# Sheet1.net
KiCad netlist of a schematic drawn in Altium Designer
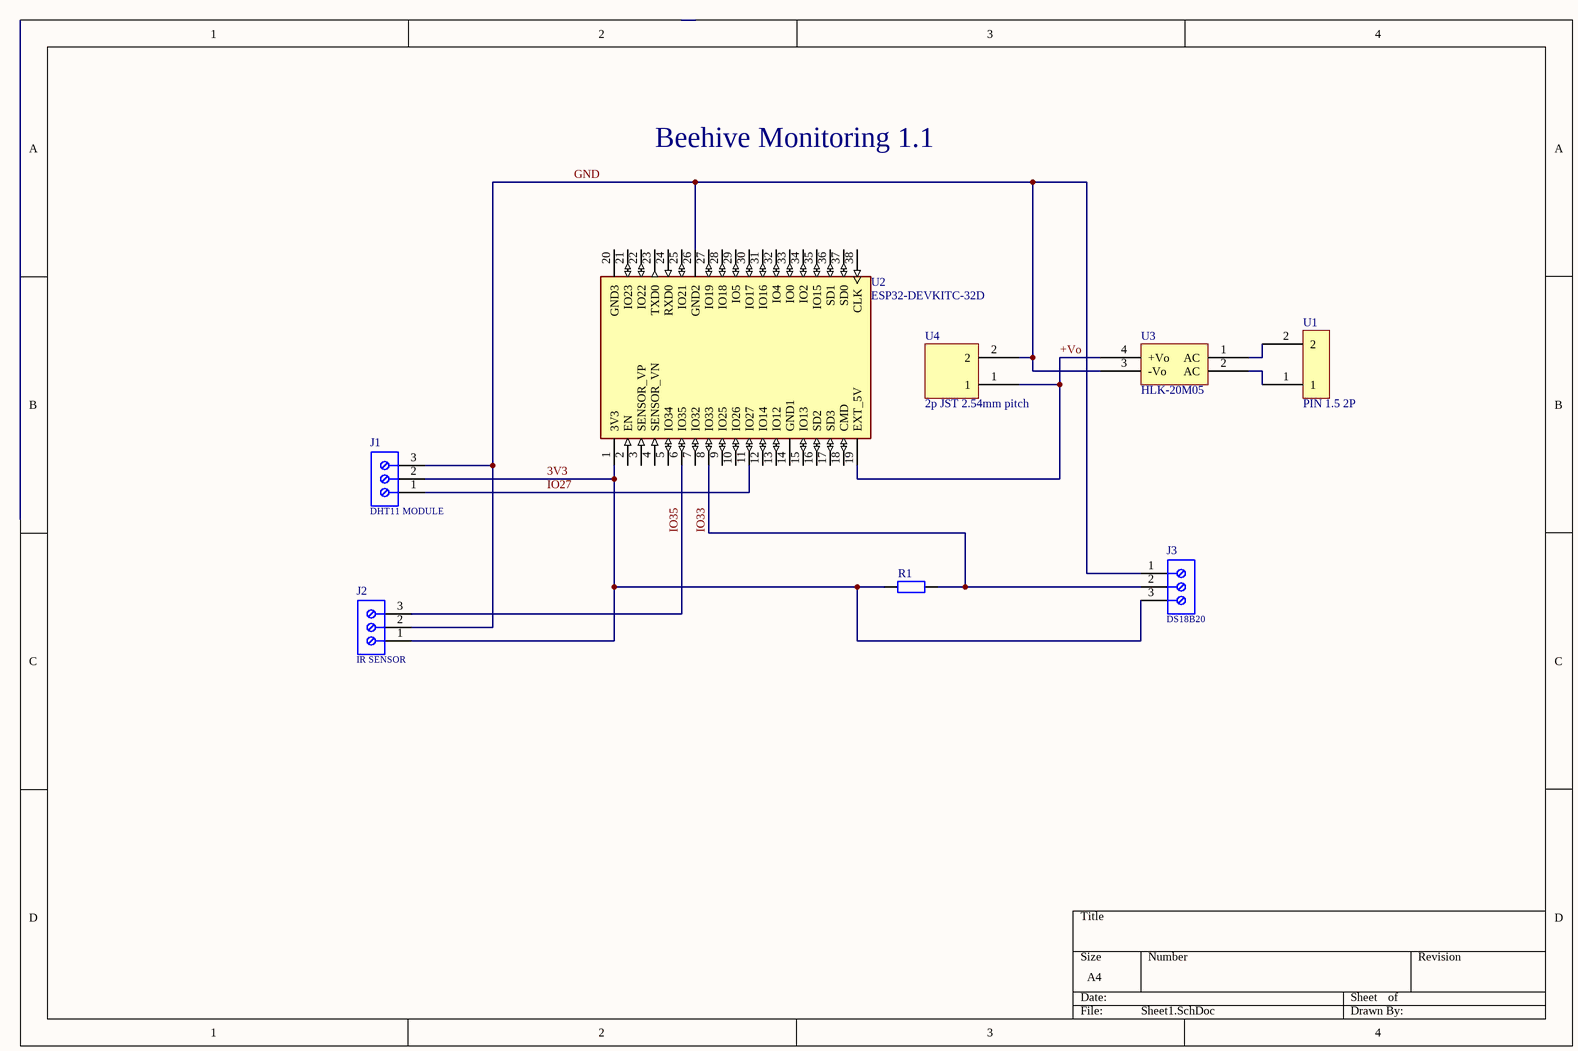
[diagram p0: Sheet1.SchDoc]

(export (version "E")
  (design (tool "Eeschema 10.0.6"))
  (components
    (comp (ref "J1")
      (value "DHT11 MODULE")
      (footprint "691214110003")
      (description "Serie 2141 - 3.50 mm Horizontal Entry Modular with Rising Cage Clamp WR-TBL, 3 pin")
      (fields
        (field (name "MANUFACTURER") "Wurth Elektronik")
        (field (name "PART NUMBER") "691214110003")
        (field (name "PUBLISHER") "WurthElektronik")
      )
      (libsource (lib "Altium Content Vault") (part "WE-CN-1P-F-TB3"))
    )
    (comp (ref "J2")
      (value "IR SENSOR")
      (footprint "691214110003")
      (description "Serie 2141 - 3.50 mm Horizontal Entry Modular with Rising Cage Clamp WR-TBL, 3 pin")
      (fields
        (field (name "MANUFACTURER") "Wurth Elektronik")
        (field (name "PART NUMBER") "691214110003")
        (field (name "PUBLISHER") "WurthElektronik")
      )
      (libsource (lib "Altium Content Vault") (part "WE-CN-1P-F-TB3"))
    )
    (comp (ref "J3")
      (value "DS18B20")
      (footprint "691214110003")
      (description "Serie 2141 - 3.50 mm Horizontal Entry Modular with Rising Cage Clamp WR-TBL, 3 pin")
      (fields
        (field (name "MANUFACTURER") "Wurth Elektronik")
        (field (name "PART NUMBER") "691214110003")
        (field (name "PUBLISHER") "WurthElektronik")
      )
      (libsource (lib "Altium Content Vault") (part "WE-CN-1P-F-TB3"))
    )
    (comp (ref "R1")
      (value "Res2")
      (footprint "AXIAL-0.4")
      (description "Resistor")
      (fields (field (name "PUBLISHER") "Altium Limited"))
      (libsource (lib "Miscellaneous Devices") (part "Res2"))
    )
    (comp (ref "U1")
      (value "PIN 1.5 2P")
      (footprint "PIN 1.5MM 2PIN")
      (description "BORNERA 1.5MM 2.8MM 2P")
      (libsource (lib "Schlib1") (part "PIN 1.5 2P"))
    )
    (comp (ref "U2")
      (value "ESP32-DEVKITC-32D")
      (footprint "MODULE_ESP32-DEVKITC-32D")
      (description "EVAL BOARD FOR ESP-WROOM-32")
      (fields (field (name "MF") "Espressif Systems"))
      (libsource (lib "ESP32-DEVKITC-32D") (part "ESP32-DEVKITC-32D"))
    )
    (comp (ref "U3")
      (value "HLK-20M05")
      (footprint "HLK-20M05")
      (libsource (lib "Schlib1") (part "HLK-20M05"))
    )
    (comp (ref "U4")
      (value "2p JST 2.54mm pitch")
      (footprint "PCBComponent_1")
      (libsource (lib "Schlib1") (part "Component_1"))
    )
  )
  (nets
    (net (code "1") (name "/+Vo") (class "Default")
      (node (ref "U2") (pin "19") (pinfunction "EXT_5V_19") (pintype "power_in"))
      (node (ref "U3") (pin "4") (pinfunction "+Vo_4") (pintype "passive"))
      (node (ref "U4") (pin "1") (pinfunction "1_1") (pintype "passive"))
    )
    (net (code "2") (name "/3V3") (class "Default")
      (node (ref "J1") (pin "2") (pinfunction "2_2") (pintype "passive"))
      (node (ref "J2") (pin "1") (pinfunction "1_1") (pintype "passive"))
      (node (ref "J3") (pin "3") (pinfunction "3_3") (pintype "passive"))
      (node (ref "R1") (pin "1") (pinfunction "1_1") (pintype "passive"))
      (node (ref "U2") (pin "1") (pinfunction "3V3_1") (pintype "power_in"))
    )
    (net (code "3") (name "/GND") (class "Default")
      (node (ref "J1") (pin "3") (pinfunction "3_3") (pintype "passive"))
      (node (ref "J2") (pin "2") (pinfunction "2_2") (pintype "passive"))
      (node (ref "J3") (pin "1") (pinfunction "1_1") (pintype "passive"))
      (node (ref "U2") (pin "26") (pinfunction "GND2_26") (pintype "power_in"))
      (node (ref "U3") (pin "3") (pinfunction "-Vo_3") (pintype "passive"))
      (node (ref "U4") (pin "2") (pinfunction "2_2") (pintype "passive"))
    )
    (net (code "4") (name "/IO27") (class "Default")
      (node (ref "J1") (pin "1") (pinfunction "1_1") (pintype "passive"))
      (node (ref "U2") (pin "11") (pinfunction "IO27_11") (pintype "bidirectional"))
    )
    (net (code "5") (name "/IO33") (class "Default")
      (node (ref "J3") (pin "2") (pinfunction "2_2") (pintype "passive"))
      (node (ref "R1") (pin "2") (pinfunction "2_2") (pintype "passive"))
      (node (ref "U2") (pin "8") (pinfunction "IO33_8") (pintype "bidirectional"))
    )
    (net (code "6") (name "/IO35") (class "Default")
      (node (ref "J2") (pin "3") (pinfunction "3_3") (pintype "passive"))
      (node (ref "U2") (pin "6") (pinfunction "IO35_6") (pintype "bidirectional"))
    )
    (net (code "7") (name "Net-(U1-Pad1)") (class "Default")
      (node (ref "U1") (pin "1") (pinfunction "1_1") (pintype "passive"))
      (node (ref "U3") (pin "2") (pinfunction "AC_2") (pintype "passive"))
    )
    (net (code "8") (name "Net-(U1-Pad2)") (class "Default")
      (node (ref "U1") (pin "2") (pinfunction "2_2") (pintype "passive"))
      (node (ref "U3") (pin "1") (pinfunction "AC_1") (pintype "passive"))
    )
    (net (code "9") (name "unconnected-(U2-CLK-Pad38)") (class "Default")
      (node (ref "U2") (pin "38") (pinfunction "CLK_38") (pintype "input"))
    )
    (net (code "10") (name "unconnected-(U2-CMD-Pad18)") (class "Default")
      (node (ref "U2") (pin "18") (pinfunction "CMD_18") (pintype "bidirectional"))
    )
    (net (code "11") (name "unconnected-(U2-EN-Pad2)") (class "Default")
      (node (ref "U2") (pin "2") (pinfunction "EN_2") (pintype "input"))
    )
    (net (code "12") (name "unconnected-(U2-GND1-Pad14)") (class "Default")
      (node (ref "U2") (pin "14") (pinfunction "GND1_14") (pintype "power_in"))
    )
    (net (code "13") (name "unconnected-(U2-GND3-Pad20)") (class "Default")
      (node (ref "U2") (pin "20") (pinfunction "GND3_20") (pintype "power_in"))
    )
    (net (code "14") (name "unconnected-(U2-IO0-Pad33)") (class "Default")
      (node (ref "U2") (pin "33") (pinfunction "IO0_33") (pintype "bidirectional"))
    )
    (net (code "15") (name "unconnected-(U2-IO2-Pad34)") (class "Default")
      (node (ref "U2") (pin "34") (pinfunction "IO2_34") (pintype "bidirectional"))
    )
    (net (code "16") (name "unconnected-(U2-IO4-Pad32)") (class "Default")
      (node (ref "U2") (pin "32") (pinfunction "IO4_32") (pintype "bidirectional"))
    )
    (net (code "17") (name "unconnected-(U2-IO5-Pad29)") (class "Default")
      (node (ref "U2") (pin "29") (pinfunction "IO5_29") (pintype "bidirectional"))
    )
    (net (code "18") (name "unconnected-(U2-IO12-Pad13)") (class "Default")
      (node (ref "U2") (pin "13") (pinfunction "IO12_13") (pintype "bidirectional"))
    )
    (net (code "19") (name "unconnected-(U2-IO13-Pad15)") (class "Default")
      (node (ref "U2") (pin "15") (pinfunction "IO13_15") (pintype "bidirectional"))
    )
    (net (code "20") (name "unconnected-(U2-IO14-Pad12)") (class "Default")
      (node (ref "U2") (pin "12") (pinfunction "IO14_12") (pintype "bidirectional"))
    )
    (net (code "21") (name "unconnected-(U2-IO15-Pad35)") (class "Default")
      (node (ref "U2") (pin "35") (pinfunction "IO15_35") (pintype "bidirectional"))
    )
    (net (code "22") (name "unconnected-(U2-IO16-Pad31)") (class "Default")
      (node (ref "U2") (pin "31") (pinfunction "IO16_31") (pintype "bidirectional"))
    )
    (net (code "23") (name "unconnected-(U2-IO17-Pad30)") (class "Default")
      (node (ref "U2") (pin "30") (pinfunction "IO17_30") (pintype "bidirectional"))
    )
    (net (code "24") (name "unconnected-(U2-IO18-Pad28)") (class "Default")
      (node (ref "U2") (pin "28") (pinfunction "IO18_28") (pintype "bidirectional"))
    )
    (net (code "25") (name "unconnected-(U2-IO19-Pad27)") (class "Default")
      (node (ref "U2") (pin "27") (pinfunction "IO19_27") (pintype "bidirectional"))
    )
    (net (code "26") (name "unconnected-(U2-IO21-Pad25)") (class "Default")
      (node (ref "U2") (pin "25") (pinfunction "IO21_25") (pintype "bidirectional"))
    )
    (net (code "27") (name "unconnected-(U2-IO22-Pad22)") (class "Default")
      (node (ref "U2") (pin "22") (pinfunction "IO22_22") (pintype "bidirectional"))
    )
    (net (code "28") (name "unconnected-(U2-IO23-Pad21)") (class "Default")
      (node (ref "U2") (pin "21") (pinfunction "IO23_21") (pintype "bidirectional"))
    )
    (net (code "29") (name "unconnected-(U2-IO25-Pad9)") (class "Default")
      (node (ref "U2") (pin "9") (pinfunction "IO25_9") (pintype "bidirectional"))
    )
    (net (code "30") (name "unconnected-(U2-IO26-Pad10)") (class "Default")
      (node (ref "U2") (pin "10") (pinfunction "IO26_10") (pintype "bidirectional"))
    )
    (net (code "31") (name "unconnected-(U2-IO32-Pad7)") (class "Default")
      (node (ref "U2") (pin "7") (pinfunction "IO32_7") (pintype "bidirectional"))
    )
    (net (code "32") (name "unconnected-(U2-IO34-Pad5)") (class "Default")
      (node (ref "U2") (pin "5") (pinfunction "IO34_5") (pintype "bidirectional"))
    )
    (net (code "33") (name "unconnected-(U2-RXD0-Pad24)") (class "Default")
      (node (ref "U2") (pin "24") (pinfunction "RXD0_24") (pintype "input"))
    )
    (net (code "34") (name "unconnected-(U2-SD0-Pad37)") (class "Default")
      (node (ref "U2") (pin "37") (pinfunction "SD0_37") (pintype "bidirectional"))
    )
    (net (code "35") (name "unconnected-(U2-SD1-Pad36)") (class "Default")
      (node (ref "U2") (pin "36") (pinfunction "SD1_36") (pintype "bidirectional"))
    )
    (net (code "36") (name "unconnected-(U2-SD2-Pad16)") (class "Default")
      (node (ref "U2") (pin "16") (pinfunction "SD2_16") (pintype "bidirectional"))
    )
    (net (code "37") (name "unconnected-(U2-SD3-Pad17)") (class "Default")
      (node (ref "U2") (pin "17") (pinfunction "SD3_17") (pintype "bidirectional"))
    )
    (net (code "38") (name "unconnected-(U2-SENSOR_VN-Pad4)") (class "Default")
      (node (ref "U2") (pin "4") (pinfunction "SENSOR_VN_4") (pintype "input"))
    )
    (net (code "39") (name "unconnected-(U2-SENSOR_VP-Pad3)") (class "Default")
      (node (ref "U2") (pin "3") (pinfunction "SENSOR_VP_3") (pintype "input"))
    )
    (net (code "40") (name "unconnected-(U2-TXD0-Pad23)") (class "Default")
      (node (ref "U2") (pin "23") (pinfunction "TXD0_23") (pintype "output"))
    )
  )
)
